# Main.net
KiCad netlist of a schematic drawn in Altium Designer
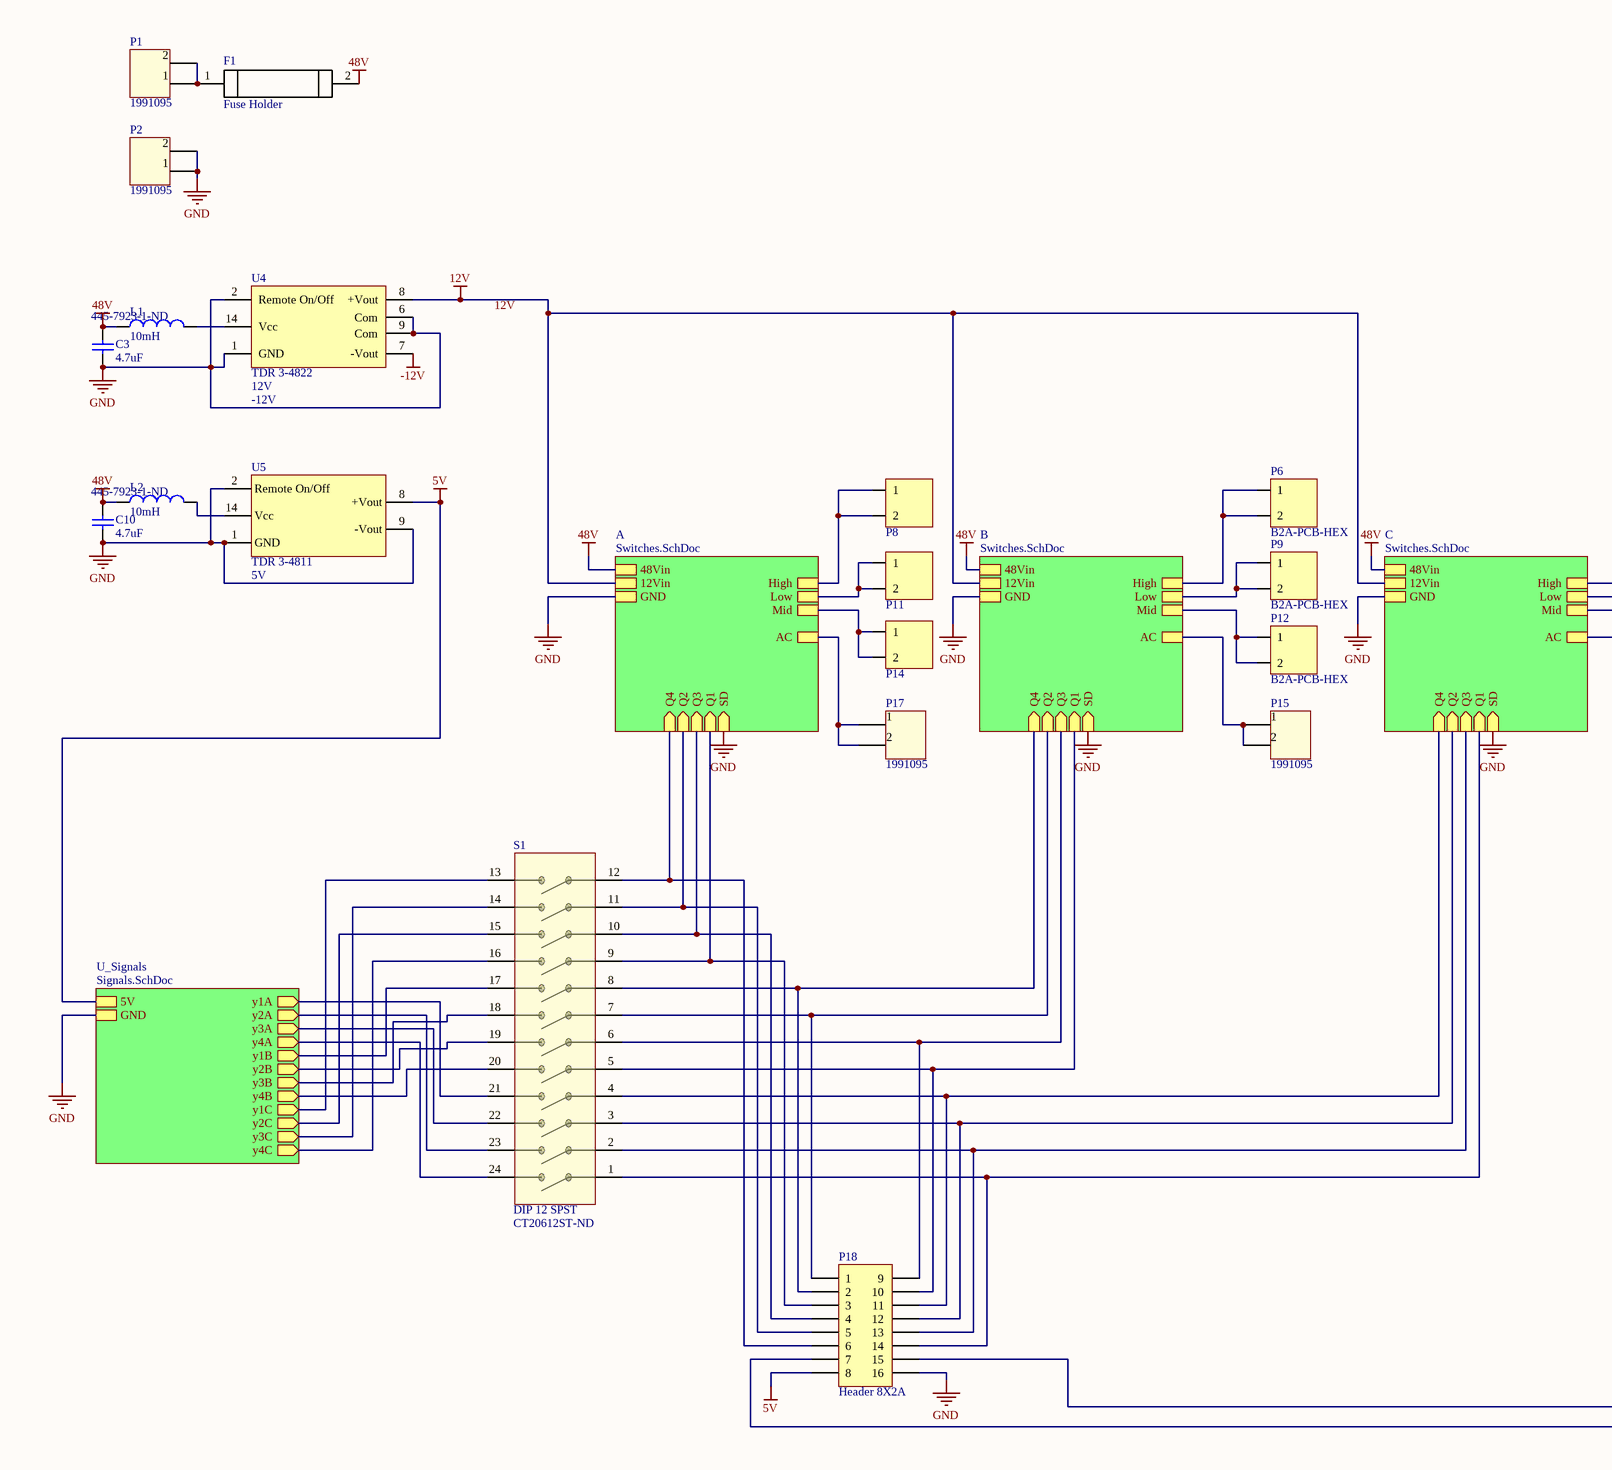
[diagram p0: Main.SchDoc, left]
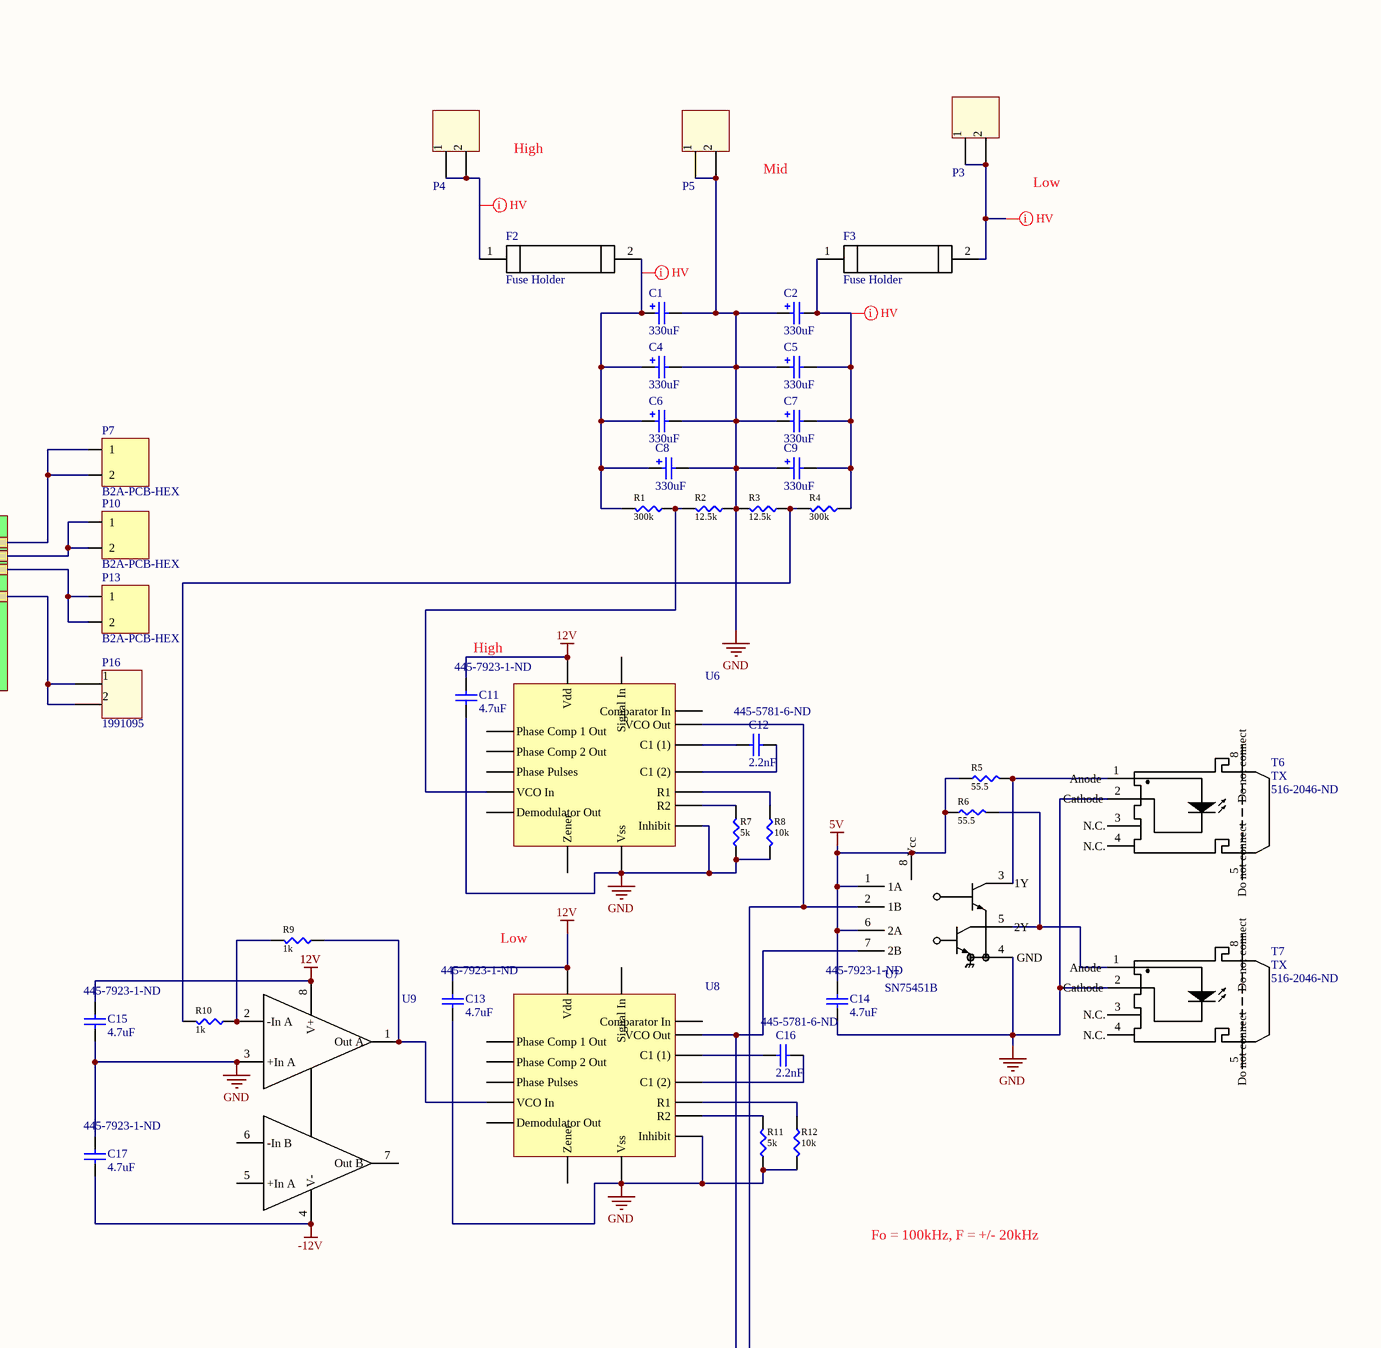
[diagram p1: Main.SchDoc, right]

(export (version "E")
  (design (tool "Eeschema 10.0.6"))
  (components
    (comp (ref "C1")
      (value "330uF")
      (footprint "LGW2G331MELB40")
      (description "Polarized Capacitor (Radial)")
      (fields
        (field (name "MANUFACTURER") "Nichicon")
        (field (name "MANUFACTURER PART NUMBER") "LGW2G331MELB40")
        (field (name "PUBLISHER") "Altium Limited")
      )
      (libsource (lib "T-Type Converter") (part "Cap Pol1"))
    )
    (comp (ref "C2")
      (value "330uF")
      (footprint "LGW2G331MELB40")
      (description "Polarized Capacitor (Radial)")
      (fields
        (field (name "MANUFACTURER") "Nichicon")
        (field (name "MANUFACTURER PART NUMBER") "LGW2G331MELB40")
        (field (name "PUBLISHER") "Altium Limited")
      )
      (libsource (lib "T-Type Converter") (part "Cap Pol1"))
    )
    (comp (ref "C3")
      (value "4.7uF")
      (footprint "C4532")
      (description "Capacitor")
      (fields
        (field (name "SUPPLIER PART NUMBER 1") "445-7923-1-ND")
        (field (name "MANUFACTURER") "TDK")
        (field (name "MANUFACTURER PART NUMBER") "CGA8N3X7S2A475K230KB")
        (field (name "PUBLISHER") "Altium Limited")
      )
      (libsource (lib "T-Type Converter") (part "Cap"))
    )
    (comp (ref "C4")
      (value "330uF")
      (footprint "LGW2G331MELB40")
      (description "Polarized Capacitor (Radial)")
      (fields
        (field (name "MANUFACTURER") "Nichicon")
        (field (name "MANUFACTURER PART NUMBER") "LGW2G331MELB40")
        (field (name "PUBLISHER") "Altium Limited")
      )
      (libsource (lib "T-Type Converter") (part "Cap Pol1"))
    )
    (comp (ref "C5")
      (value "330uF")
      (footprint "LGW2G331MELB40")
      (description "Polarized Capacitor (Radial)")
      (fields
        (field (name "MANUFACTURER") "Nichicon")
        (field (name "MANUFACTURER PART NUMBER") "LGW2G331MELB40")
        (field (name "PUBLISHER") "Altium Limited")
      )
      (libsource (lib "T-Type Converter") (part "Cap Pol1"))
    )
    (comp (ref "C6")
      (value "330uF")
      (footprint "LGW2G331MELB40")
      (description "Polarized Capacitor (Radial)")
      (fields
        (field (name "MANUFACTURER") "Nichicon")
        (field (name "MANUFACTURER PART NUMBER") "LGW2G331MELB40")
        (field (name "PUBLISHER") "Altium Limited")
      )
      (libsource (lib "T-Type Converter") (part "Cap Pol1"))
    )
    (comp (ref "C7")
      (value "330uF")
      (footprint "LGW2G331MELB40")
      (description "Polarized Capacitor (Radial)")
      (fields
        (field (name "MANUFACTURER") "Nichicon")
        (field (name "MANUFACTURER PART NUMBER") "LGW2G331MELB40")
        (field (name "PUBLISHER") "Altium Limited")
      )
      (libsource (lib "T-Type Converter") (part "Cap Pol1"))
    )
    (comp (ref "C8")
      (value "330uF")
      (footprint "LGW2G331MELB40")
      (description "Polarized Capacitor (Radial)")
      (fields
        (field (name "MANUFACTURER") "Nichicon")
        (field (name "MANUFACTURER PART NUMBER") "LGW2G331MELB40")
        (field (name "PUBLISHER") "Altium Limited")
      )
      (libsource (lib "T-Type Converter") (part "Cap Pol1"))
    )
    (comp (ref "C9")
      (value "330uF")
      (footprint "LGW2G331MELB40")
      (description "Polarized Capacitor (Radial)")
      (fields
        (field (name "MANUFACTURER") "Nichicon")
        (field (name "MANUFACTURER PART NUMBER") "LGW2G331MELB40")
        (field (name "PUBLISHER") "Altium Limited")
      )
      (libsource (lib "T-Type Converter") (part "Cap Pol1"))
    )
    (comp (ref "C10")
      (value "4.7uF")
      (footprint "C4532")
      (description "Capacitor")
      (fields
        (field (name "SUPPLIER PART NUMBER 1") "445-7923-1-ND")
        (field (name "MANUFACTURER") "TDK")
        (field (name "MANUFACTURER PART NUMBER") "CGA8N3X7S2A475K230KB")
        (field (name "PUBLISHER") "Altium Limited")
      )
      (libsource (lib "T-Type Converter") (part "Cap"))
    )
    (comp (ref "C11")
      (value "4.7uF")
      (footprint "C4532")
      (description "Capacitor")
      (fields
        (field (name "SUPPLIER PART NUMBER 1") "445-7923-1-ND")
        (field (name "MANUFACTURER") "TDK")
        (field (name "MANUFACTURER PART NUMBER") "CGA8N3X7S2A475K230KB")
        (field (name "PUBLISHER") "Altium Limited")
      )
      (libsource (lib "T-Type Converter") (part "Cap"))
    )
    (comp (ref "C12")
      (value "2.2nF")
      (footprint "R_1206")
      (description "Capacitor")
      (fields
        (field (name "SUPPLIER PART NUMBER 1") "445-5781-6-ND")
        (field (name "MANUFACTURER") "TDK")
        (field (name "MANUFACTURER PART NUMBER") "CGA5C4C0G2J221J060AA")
      )
      (libsource (lib "T-Type Converter") (part "Cap"))
    )
    (comp (ref "C13")
      (value "4.7uF")
      (footprint "C4532")
      (description "Capacitor")
      (fields
        (field (name "SUPPLIER PART NUMBER 1") "445-7923-1-ND")
        (field (name "MANUFACTURER") "TDK")
        (field (name "MANUFACTURER PART NUMBER") "CGA8N3X7S2A475K230KB")
        (field (name "PUBLISHER") "Altium Limited")
      )
      (libsource (lib "T-Type Converter") (part "Cap"))
    )
    (comp (ref "C14")
      (value "4.7uF")
      (footprint "C4532")
      (description "Capacitor")
      (fields
        (field (name "SUPPLIER PART NUMBER 1") "445-7923-1-ND")
        (field (name "MANUFACTURER") "TDK")
        (field (name "MANUFACTURER PART NUMBER") "CGA8N3X7S2A475K230KB")
        (field (name "PUBLISHER") "Altium Limited")
      )
      (libsource (lib "T-Type Converter") (part "Cap"))
    )
    (comp (ref "C15")
      (value "4.7uF")
      (footprint "C4532")
      (description "Capacitor")
      (fields
        (field (name "SUPPLIER PART NUMBER 1") "445-7923-1-ND")
        (field (name "MANUFACTURER") "TDK")
        (field (name "MANUFACTURER PART NUMBER") "CGA8N3X7S2A475K230KB")
        (field (name "PUBLISHER") "Altium Limited")
      )
      (libsource (lib "T-Type Converter") (part "Cap"))
    )
    (comp (ref "C16")
      (value "2.2nF")
      (footprint "R_1206")
      (description "Capacitor")
      (fields
        (field (name "SUPPLIER PART NUMBER 1") "445-5781-6-ND")
        (field (name "MANUFACTURER") "TDK")
        (field (name "MANUFACTURER PART NUMBER") "CGA5C4C0G2J221J060AA")
      )
      (libsource (lib "T-Type Converter") (part "Cap"))
    )
    (comp (ref "C17")
      (value "4.7uF")
      (footprint "C4532")
      (description "Capacitor")
      (fields
        (field (name "SUPPLIER PART NUMBER 1") "445-7923-1-ND")
        (field (name "MANUFACTURER") "TDK")
        (field (name "MANUFACTURER PART NUMBER") "CGA8N3X7S2A475K230KB")
        (field (name "PUBLISHER") "Altium Limited")
      )
      (libsource (lib "T-Type Converter") (part "Cap"))
    )
    (comp (ref "F1")
      (value "Fuse Holder")
      (footprint "Small Fuse Holder")
      (fields
        (field (name "MANUFACTURER") "Littelfuse")
        (field (name "MANUFACTURER PART NUMBER") "01220093Z")
        (field (name "VOLTAGE") "250V")
      )
      (libsource (lib "T-Type Converter") (part "Fuse Holder"))
    )
    (comp (ref "F2")
      (value "Fuse Holder")
      (footprint "Fuse footprint")
      (fields
        (field (name "MANUFACTURER") "Littelfuse")
        (field (name "MANUFACTURER PART NUMBER") "01220093Z")
        (field (name "VOLTAGE") "250V")
      )
      (libsource (lib "T-Type Converter") (part "Fuse Holder"))
    )
    (comp (ref "F3")
      (value "Fuse Holder")
      (footprint "Fuse footprint")
      (fields
        (field (name "MANUFACTURER") "Littelfuse")
        (field (name "MANUFACTURER PART NUMBER") "01220093Z")
        (field (name "VOLTAGE") "250V")
      )
      (libsource (lib "T-Type Converter") (part "Fuse Holder"))
    )
    (comp (ref "L1")
      (value "10mH")
      (footprint "TCK-047")
      (description "Inductor")
      (fields (field (name "PUBLISHER") "Altium Limited"))
      (libsource (lib "Miscellaneous Devices") (part "Inductor"))
    )
    (comp (ref "L2")
      (value "10mH")
      (footprint "TCK-047")
      (description "Inductor")
      (fields (field (name "PUBLISHER") "Altium Limited"))
      (libsource (lib "Miscellaneous Devices") (part "Inductor"))
    )
    (comp (ref "P1")
      (value "1991095")
      (footprint "Terminal Pad")
      (description "2 way terminal block")
      (fields (field (name "MANUFACTURER") "Phoenix Contact") (field (name "VOLTAGE") "300V"))
      (libsource (lib "") (part "Terminal Block 2_1"))
    )
    (comp (ref "P2")
      (value "1991095")
      (footprint "Terminal Pad")
      (description "2 way terminal block")
      (fields (field (name "MANUFACTURER") "Phoenix Contact") (field (name "VOLTAGE") "300V"))
      (libsource (lib "") (part "Terminal Block 2_1"))
    )
    (comp (ref "P3")
      (value "1991095")
      (footprint "Terminal Pad")
      (description "2 way terminal block")
      (fields (field (name "MANUFACTURER") "Phoenix Contact") (field (name "VOLTAGE") "300V"))
      (libsource (lib "") (part "Terminal Block 2_2"))
    )
    (comp (ref "P4")
      (value "1991095")
      (footprint "Terminal Pad")
      (description "2 way terminal block")
      (fields (field (name "MANUFACTURER") "Phoenix Contact") (field (name "VOLTAGE") "300V"))
      (libsource (lib "") (part "Terminal Block 2_2"))
    )
    (comp (ref "P5")
      (value "1991095")
      (footprint "Terminal Pad")
      (description "2 way terminal block")
      (fields (field (name "MANUFACTURER") "Phoenix Contact") (field (name "VOLTAGE") "300V"))
      (libsource (lib "") (part "Terminal Block 2_2"))
    )
    (comp (ref "P6")
      (value "B2A-PCB-HEX")
      (footprint "Terminal Pad")
      (libsource (lib "T-Type Converter") (part "B2A-PCB-HEX"))
    )
    (comp (ref "P7")
      (value "B2A-PCB-HEX")
      (footprint "Terminal Pad")
      (libsource (lib "T-Type Converter") (part "B2A-PCB-HEX"))
    )
    (comp (ref "P8")
      (value "B2A-PCB-HEX")
      (footprint "Terminal Pad")
      (libsource (lib "T-Type Converter") (part "B2A-PCB-HEX"))
    )
    (comp (ref "P9")
      (value "B2A-PCB-HEX")
      (footprint "Terminal Pad")
      (libsource (lib "T-Type Converter") (part "B2A-PCB-HEX"))
    )
    (comp (ref "P10")
      (value "B2A-PCB-HEX")
      (footprint "Terminal Pad")
      (libsource (lib "T-Type Converter") (part "B2A-PCB-HEX"))
    )
    (comp (ref "P11")
      (value "B2A-PCB-HEX")
      (footprint "Terminal Pad")
      (libsource (lib "T-Type Converter") (part "B2A-PCB-HEX"))
    )
    (comp (ref "P12")
      (value "B2A-PCB-HEX")
      (footprint "Terminal Pad")
      (libsource (lib "T-Type Converter") (part "B2A-PCB-HEX"))
    )
    (comp (ref "P13")
      (value "B2A-PCB-HEX")
      (footprint "Terminal Pad")
      (libsource (lib "T-Type Converter") (part "B2A-PCB-HEX"))
    )
    (comp (ref "P14")
      (value "B2A-PCB-HEX")
      (footprint "Terminal Pad")
      (libsource (lib "T-Type Converter") (part "B2A-PCB-HEX"))
    )
    (comp (ref "P15")
      (value "1991095")
      (footprint "Terminal Pad")
      (description "2 way terminal block")
      (fields (field (name "MANUFACTURER") "Phoenix Contact") (field (name "VOLTAGE") "300V"))
      (libsource (lib "T-Type Converter") (part "Terminal Block 2"))
    )
    (comp (ref "P16")
      (value "1991095")
      (footprint "Terminal Pad")
      (description "2 way terminal block")
      (fields (field (name "MANUFACTURER") "Phoenix Contact") (field (name "VOLTAGE") "300V"))
      (libsource (lib "T-Type Converter") (part "Terminal Block 2"))
    )
    (comp (ref "P17")
      (value "1991095")
      (footprint "Terminal Pad")
      (description "2 way terminal block")
      (fields (field (name "MANUFACTURER") "Phoenix Contact") (field (name "VOLTAGE") "300V"))
      (libsource (lib "T-Type Converter") (part "Terminal Block 2"))
    )
    (comp (ref "P18")
      (value "Header 8X2A")
      (footprint "302-S161")
      (description "Header, 8-Pin, Dual row")
      (fields
        (field (name "MANUFACTURER") "On-Shore Technology")
        (field (name "MANUFACTURER PART NUMBER") "302-S161")
        (field (name "PUBLISHER") "Altium Limited")
      )
      (libsource (lib "Miscellaneous Connectors") (part "Header 8X2A"))
    )
    (comp (ref "R1")
      (value "300k")
      (footprint "R_1206")
      (description "RES SMD 1% 1/4W 1206")
      (fields
        (field (name "MANUFACTURER") "Panasonic Electronic Components")
        (field (name "MANUFACTURER PART NUMBER") "ERJ-8ENF9101V")
      )
      (libsource (lib "T-Type Converter") (part "RES_SMD1"))
    )
    (comp (ref "R2")
      (value "12.5k")
      (footprint "R_1206")
      (description "RES SMD 1% 1/4W 1206")
      (fields
        (field (name "MANUFACTURER") "Panasonic Electronic Components")
        (field (name "MANUFACTURER PART NUMBER") "ERJ-8ENF9101V")
      )
      (libsource (lib "T-Type Converter") (part "RES_SMD1"))
    )
    (comp (ref "R3")
      (value "12.5k")
      (footprint "R_1206")
      (description "RES SMD 1% 1/4W 1206")
      (fields
        (field (name "MANUFACTURER") "Panasonic Electronic Components")
        (field (name "MANUFACTURER PART NUMBER") "ERJ-8ENF9101V")
      )
      (libsource (lib "T-Type Converter") (part "RES_SMD1"))
    )
    (comp (ref "R4")
      (value "300k")
      (footprint "R_1206")
      (description "RES SMD 1% 1/4W 1206")
      (fields
        (field (name "MANUFACTURER") "Panasonic Electronic Components")
        (field (name "MANUFACTURER PART NUMBER") "ERJ-8ENF9101V")
      )
      (libsource (lib "T-Type Converter") (part "RES_SMD1"))
    )
    (comp (ref "R5")
      (value "55.5")
      (footprint "R_1206")
      (description "RES SMD 1% 1/4W 1206")
      (fields
        (field (name "MANUFACTURER") "Panasonic Electronic Components")
        (field (name "MANUFACTURER PART NUMBER") "ERJ-8ENF9101V")
      )
      (libsource (lib "T-Type Converter") (part "RES_SMD1"))
    )
    (comp (ref "R6")
      (value "55.5")
      (footprint "R_1206")
      (description "RES SMD 1% 1/4W 1206")
      (fields
        (field (name "MANUFACTURER") "Panasonic Electronic Components")
        (field (name "MANUFACTURER PART NUMBER") "ERJ-8ENF9101V")
      )
      (libsource (lib "T-Type Converter") (part "RES_SMD1"))
    )
    (comp (ref "R7")
      (value "5k")
      (footprint "R_1206")
      (description "RES SMD 1% 1/4W 1206")
      (fields
        (field (name "MANUFACTURER") "Panasonic Electronic Components")
        (field (name "MANUFACTURER PART NUMBER") "ERJ-8ENF9101V")
      )
      (libsource (lib "T-Type Converter") (part "RES_SMD1"))
    )
    (comp (ref "R8")
      (value "10k")
      (footprint "R_1206")
      (description "RES SMD 1% 1/4W 1206")
      (fields
        (field (name "MANUFACTURER") "Panasonic Electronic Components")
        (field (name "MANUFACTURER PART NUMBER") "ERJ-8ENF9101V")
      )
      (libsource (lib "T-Type Converter") (part "RES_SMD1"))
    )
    (comp (ref "R9")
      (value "1k")
      (footprint "R_1206")
      (description "RES SMD 1% 1/4W 1206")
      (fields
        (field (name "MANUFACTURER") "Panasonic Electronic Components")
        (field (name "MANUFACTURER PART NUMBER") "ERJ-8ENF9101V")
      )
      (libsource (lib "T-Type Converter") (part "RES_SMD1"))
    )
    (comp (ref "R10")
      (value "1k")
      (footprint "R_1206")
      (description "RES SMD 1% 1/4W 1206")
      (fields
        (field (name "MANUFACTURER") "Panasonic Electronic Components")
        (field (name "MANUFACTURER PART NUMBER") "ERJ-8ENF9101V")
      )
      (libsource (lib "T-Type Converter") (part "RES_SMD1"))
    )
    (comp (ref "R11")
      (value "5k")
      (footprint "R_1206")
      (description "RES SMD 1% 1/4W 1206")
      (fields
        (field (name "MANUFACTURER") "Panasonic Electronic Components")
        (field (name "MANUFACTURER PART NUMBER") "ERJ-8ENF9101V")
      )
      (libsource (lib "T-Type Converter") (part "RES_SMD1"))
    )
    (comp (ref "R12")
      (value "10k")
      (footprint "R_1206")
      (description "RES SMD 1% 1/4W 1206")
      (fields
        (field (name "MANUFACTURER") "Panasonic Electronic Components")
        (field (name "MANUFACTURER PART NUMBER") "ERJ-8ENF9101V")
      )
      (libsource (lib "T-Type Converter") (part "RES_SMD1"))
    )
    (comp (ref "S1")
      (value "DIP 12 SPST")
      (footprint "DIP12 SPST")
      (fields
        (field (name "MANUFACTURER") "CTS Electrocomponents")
        (field (name "MANUFACTURER PART NUMBER") "206-12ST")
        (field (name "SUPPLIER PART NUMBER 1") "CT20612ST-ND")
      )
      (libsource (lib "T-Type Converter") (part "DIP 12 SPST"))
    )
    (comp (ref "T6")
      (value "TX")
      (footprint "Optics")
      (description "Otical Transmitter")
      (fields
        (field (name "MANUFACTURER") "Broadcom Avago")
        (field (name "MANUFACTURER PART NUMBER") "HFBR-1524Z")
        (field (name "SUPPLIER PART NUMBER 1") "516-2046-ND")
      )
      (libsource (lib "T-Type Converter") (part "HFBR-1524Z"))
    )
    (comp (ref "T7")
      (value "TX")
      (footprint "Optics")
      (description "Otical Transmitter")
      (fields
        (field (name "MANUFACTURER") "Broadcom Avago")
        (field (name "MANUFACTURER PART NUMBER") "HFBR-1524Z")
        (field (name "SUPPLIER PART NUMBER 1") "516-2046-ND")
      )
      (libsource (lib "T-Type Converter") (part "HFBR-1524Z"))
    )
    (comp (ref "U4")
      (value "TDR 3-4822")
      (footprint "PID DC-DC Converter - duplicate")
      (description "48 +/-12V Converter")
      (fields
        (field (name "MANUFACTURER") "Traco Power")
        (field (name "MANUFACTURER PART NUMBER") "TDR3-4822")
        (field (name "VOLTAGE - OUTPUT 1") "12V")
        (field (name "VOLTAGE - OUTPUT 2") "-12V")
      )
      (libsource (lib "T-Type Converter") (part "TDR 3-4822"))
    )
    (comp (ref "U5")
      (value "TDR 3-4811")
      (footprint "PID DC-DC Converter - duplicate")
      (description "48V-5V Converter")
      (fields
        (field (name "MANUFACTURER") "Traco Power")
        (field (name "MANUFACTURER PART NUMBER") "TDR3-4811")
        (field (name "VOLTAGE - OUTPUT 1") "5V")
      )
      (libsource (lib "T-Type Converter") (part "TDR 3-4811"))
    )
    (comp (ref "U6")
      (value "CD4046B")
      (footprint "DIP16")
      (description "VCO")
      (fields
        (field (name "MANUFACTURER") "Texas Instruments")
        (field (name "MANUFACTURER PART NUMBER") "CD4046BE")
      )
      (libsource (lib "T-Type Converter") (part "CD4046B"))
    )
    (comp (ref "U7")
      (value "SN75451B")
      (footprint "R-PDIP-T8")
      (description "Dual Peripheral Drivers")
      (fields
        (field (name "MANUFACTURER") "Texas Instruments")
        (field (name "MANUFACTURER PART NUMBER") "SN75451BP")
      )
      (libsource (lib "T-Type Converter") (part "SN75451B"))
    )
    (comp (ref "U8")
      (value "CD4046B")
      (footprint "DIP16")
      (description "VCO")
      (fields
        (field (name "MANUFACTURER") "Texas Instruments")
        (field (name "MANUFACTURER PART NUMBER") "CD4046BE")
      )
      (libsource (lib "T-Type Converter") (part "CD4046B"))
    )
    (comp (ref "U9")
      (value "LT1057CN8")
      (footprint "N8 PDIP")
      (description "Dual Op-Amp")
      (fields
        (field (name "MANUFACTURER") "STMicroelectronics")
        (field (name "MANUFACTURER PART NUMBER") "LMV321LICT")
      )
      (libsource (lib "T-Type Converter") (part "LT1057CN8"))
    )
  )
  (nets
    (net (code "1") (name "-12V") (class "Default")
      (node (ref "C17") (pin "1") (pinfunction "1_1") (pintype "passive"))
      (node (ref "U4") (pin "7") (pinfunction "-Vout_7") (pintype "passive"))
      (node (ref "U9") (pin "4") (pinfunction "V-_4") (pintype "power_in"))
    )
    (net (code "2") (name "/AC") (class "Default")
      (node (ref "P16") (pin "1") (pintype "power_in"))
      (node (ref "P16") (pin "2") (pintype "power_in"))
    )
    (net (code "3") (name "/AC_1") (class "Default")
      (node (ref "P17") (pin "1") (pintype "power_in"))
      (node (ref "P17") (pin "2") (pintype "power_in"))
    )
    (net (code "4") (name "/AC_2") (class "Default")
      (node (ref "P15") (pin "1") (pintype "power_in"))
      (node (ref "P15") (pin "2") (pintype "power_in"))
    )
    (net (code "5") (name "/High") (class "Default")
      (node (ref "P7") (pin "1") (pinfunction "1_1") (pintype "passive"))
      (node (ref "P7") (pin "2") (pinfunction "2_2") (pintype "passive"))
    )
    (net (code "6") (name "/High_1") (class "Default")
      (node (ref "P8") (pin "1") (pinfunction "1_1") (pintype "passive"))
      (node (ref "P8") (pin "2") (pinfunction "2_2") (pintype "passive"))
    )
    (net (code "7") (name "/High_2") (class "Default")
      (node (ref "P6") (pin "1") (pinfunction "1_1") (pintype "passive"))
      (node (ref "P6") (pin "2") (pinfunction "2_2") (pintype "passive"))
    )
    (net (code "8") (name "/Low") (class "Default")
      (node (ref "P10") (pin "1") (pinfunction "1_1") (pintype "passive"))
      (node (ref "P10") (pin "2") (pinfunction "2_2") (pintype "passive"))
    )
    (net (code "9") (name "/Low_1") (class "Default")
      (node (ref "P11") (pin "1") (pinfunction "1_1") (pintype "passive"))
      (node (ref "P11") (pin "2") (pinfunction "2_2") (pintype "passive"))
    )
    (net (code "10") (name "/Low_2") (class "Default")
      (node (ref "P9") (pin "1") (pinfunction "1_1") (pintype "passive"))
      (node (ref "P9") (pin "2") (pinfunction "2_2") (pintype "passive"))
    )
    (net (code "11") (name "/Mid") (class "Default")
      (node (ref "P13") (pin "1") (pinfunction "1_1") (pintype "passive"))
      (node (ref "P13") (pin "2") (pinfunction "2_2") (pintype "passive"))
    )
    (net (code "12") (name "/Mid_1") (class "Default")
      (node (ref "P14") (pin "1") (pinfunction "1_1") (pintype "passive"))
      (node (ref "P14") (pin "2") (pinfunction "2_2") (pintype "passive"))
    )
    (net (code "13") (name "/Mid_2") (class "Default")
      (node (ref "P12") (pin "1") (pinfunction "1_1") (pintype "passive"))
      (node (ref "P12") (pin "2") (pinfunction "2_2") (pintype "passive"))
    )
    (net (code "14") (name "/Q1") (class "Default")
      (node (ref "P18") (pin "14") (pinfunction "14_14") (pintype "passive"))
      (node (ref "S1") (pin "1") (pinfunction "1_1") (pintype "power_in"))
    )
    (net (code "15") (name "/Q1_1") (class "Default")
      (node (ref "P18") (pin "10") (pinfunction "10_10") (pintype "passive"))
      (node (ref "S1") (pin "5") (pinfunction "5_5") (pintype "power_in"))
    )
    (net (code "16") (name "/Q1_2") (class "Default")
      (node (ref "P18") (pin "3") (pinfunction "3_3") (pintype "passive"))
      (node (ref "S1") (pin "9") (pinfunction "9_9") (pintype "power_in"))
    )
    (net (code "17") (name "/Q2") (class "Default")
      (node (ref "P18") (pin "5") (pinfunction "5_5") (pintype "passive"))
      (node (ref "S1") (pin "11") (pinfunction "11_11") (pintype "power_in"))
    )
    (net (code "18") (name "/Q2_1") (class "Default")
      (node (ref "P18") (pin "1") (pinfunction "1_1") (pintype "passive"))
      (node (ref "S1") (pin "7") (pinfunction "7_7") (pintype "power_in"))
    )
    (net (code "19") (name "/Q2_2") (class "Default")
      (node (ref "P18") (pin "12") (pinfunction "12_12") (pintype "passive"))
      (node (ref "S1") (pin "3") (pinfunction "3_3") (pintype "power_in"))
    )
    (net (code "20") (name "/Q3") (class "Default")
      (node (ref "P18") (pin "4") (pinfunction "4_4") (pintype "passive"))
      (node (ref "S1") (pin "10") (pinfunction "10_10") (pintype "power_in"))
    )
    (net (code "21") (name "/Q3_1") (class "Default")
      (node (ref "P18") (pin "9") (pinfunction "9_9") (pintype "passive"))
      (node (ref "S1") (pin "6") (pinfunction "6_6") (pintype "power_in"))
    )
    (net (code "22") (name "/Q3_2") (class "Default")
      (node (ref "P18") (pin "13") (pinfunction "13_13") (pintype "passive"))
      (node (ref "S1") (pin "2") (pinfunction "2_2") (pintype "power_in"))
    )
    (net (code "23") (name "/Q4") (class "Default")
      (node (ref "P18") (pin "2") (pinfunction "2_2") (pintype "passive"))
      (node (ref "S1") (pin "8") (pinfunction "8_8") (pintype "power_in"))
    )
    (net (code "24") (name "/Q4_1") (class "Default")
      (node (ref "P18") (pin "11") (pinfunction "11_11") (pintype "passive"))
      (node (ref "S1") (pin "4") (pinfunction "4_4") (pintype "power_in"))
    )
    (net (code "25") (name "/Q4_2") (class "Default")
      (node (ref "P18") (pin "6") (pinfunction "6_6") (pintype "passive"))
      (node (ref "S1") (pin "12") (pinfunction "12_12") (pintype "power_in"))
    )
    (net (code "26") (name "/y1A") (class "Default")
      (node (ref "S1") (pin "21") (pinfunction "21_21") (pintype "power_in"))
    )
    (net (code "27") (name "/y1B") (class "Default")
      (node (ref "S1") (pin "17") (pinfunction "17_17") (pintype "power_in"))
    )
    (net (code "28") (name "/y1C") (class "Default")
      (node (ref "S1") (pin "13") (pinfunction "13_13") (pintype "power_in"))
    )
    (net (code "29") (name "/y2A") (class "Default")
      (node (ref "S1") (pin "23") (pinfunction "23_23") (pintype "power_in"))
    )
    (net (code "30") (name "/y2B") (class "Default")
      (node (ref "S1") (pin "19") (pinfunction "19_19") (pintype "power_in"))
    )
    (net (code "31") (name "/y2C") (class "Default")
      (node (ref "S1") (pin "15") (pinfunction "15_15") (pintype "power_in"))
    )
    (net (code "32") (name "/y3A") (class "Default")
      (node (ref "S1") (pin "22") (pinfunction "22_22") (pintype "power_in"))
    )
    (net (code "33") (name "/y3B") (class "Default")
      (node (ref "S1") (pin "18") (pinfunction "18_18") (pintype "power_in"))
    )
    (net (code "34") (name "/y3C") (class "Default")
      (node (ref "S1") (pin "14") (pinfunction "14_14") (pintype "power_in"))
    )
    (net (code "35") (name "/y4A") (class "Default")
      (node (ref "S1") (pin "24") (pinfunction "24_24") (pintype "power_in"))
    )
    (net (code "36") (name "/y4B") (class "Default")
      (node (ref "S1") (pin "20") (pinfunction "20_20") (pintype "power_in"))
    )
    (net (code "37") (name "/y4C") (class "Default")
      (node (ref "S1") (pin "16") (pinfunction "16_16") (pintype "power_in"))
    )
    (net (code "38") (name "5V") (class "Default")
      (node (ref "C14") (pin "2") (pinfunction "2_2") (pintype "passive"))
      (node (ref "P18") (pin "8") (pinfunction "8_8") (pintype "passive"))
      (node (ref "R5") (pin "2") (pinfunction "2_2") (pintype "passive"))
      (node (ref "R6") (pin "2") (pinfunction "2_2") (pintype "passive"))
      (node (ref "U5") (pin "8") (pinfunction "+Vout_8") (pintype "passive"))
      (node (ref "U7") (pin "1") (pinfunction "1A_1") (pintype "power_in"))
      (node (ref "U7") (pin "6") (pinfunction "2A_6") (pintype "power_in"))
      (node (ref "U7") (pin "8") (pinfunction "Vcc_8") (pintype "power_in"))
    )
    (net (code "39") (name "12V") (class "Default")
      (node (ref "C11") (pin "2") (pinfunction "2_2") (pintype "passive"))
      (node (ref "C13") (pin "2") (pinfunction "2_2") (pintype "passive"))
      (node (ref "C15") (pin "2") (pinfunction "2_2") (pintype "passive"))
      (node (ref "U4") (pin "8") (pinfunction "+Vout_8") (pintype "passive"))
      (node (ref "U6") (pin "16") (pinfunction "Vdd_16") (pintype "passive"))
      (node (ref "U8") (pin "16") (pinfunction "Vdd_16") (pintype "passive"))
      (node (ref "U9") (pin "8") (pinfunction "V+_8") (pintype "power_in"))
    )
    (net (code "40") (name "48V") (class "Default")
      (node (ref "C10") (pin "2") (pinfunction "2_2") (pintype "passive"))
      (node (ref "C3") (pin "2") (pinfunction "2_2") (pintype "passive"))
      (node (ref "F1") (pin "2") (pintype "power_in"))
      (node (ref "L1") (pin "1") (pinfunction "1_1") (pintype "passive"))
      (node (ref "L2") (pin "1") (pinfunction "1_1") (pintype "passive"))
    )
    (net (code "41") (name "GND") (class "Default")
      (node (ref "C1") (pin "2") (pinfunction "2_2") (pintype "passive"))
      (node (ref "C10") (pin "1") (pinfunction "1_1") (pintype "passive"))
      (node (ref "C11") (pin "1") (pinfunction "1_1") (pintype "passive"))
      (node (ref "C13") (pin "1") (pinfunction "1_1") (pintype "passive"))
      (node (ref "C14") (pin "1") (pinfunction "1_1") (pintype "passive"))
      (node (ref "C15") (pin "1") (pinfunction "1_1") (pintype "passive"))
      (node (ref "C17") (pin "2") (pinfunction "2_2") (pintype "passive"))
      (node (ref "C2") (pin "1") (pinfunction "1_1") (pintype "passive"))
      (node (ref "C3") (pin "1") (pinfunction "1_1") (pintype "passive"))
      (node (ref "C4") (pin "2") (pinfunction "2_2") (pintype "passive"))
      (node (ref "C5") (pin "1") (pinfunction "1_1") (pintype "passive"))
      (node (ref "C6") (pin "2") (pinfunction "2_2") (pintype "passive"))
      (node (ref "C7") (pin "1") (pinfunction "1_1") (pintype "passive"))
      (node (ref "C8") (pin "2") (pinfunction "2_2") (pintype "passive"))
      (node (ref "C9") (pin "1") (pinfunction "1_1") (pintype "passive"))
      (node (ref "P18") (pin "16") (pinfunction "16_16") (pintype "passive"))
      (node (ref "P2") (pin "1") (pintype "power_in"))
      (node (ref "P2") (pin "2") (pintype "power_in"))
      (node (ref "P5") (pin "1") (pintype "power_in"))
      (node (ref "P5") (pin "2") (pintype "power_in"))
      (node (ref "R11") (pin "2") (pinfunction "2_2") (pintype "passive"))
      (node (ref "R12") (pin "1") (pinfunction "1_1") (pintype "passive"))
      (node (ref "R2") (pin "2") (pinfunction "2_2") (pintype "passive"))
      (node (ref "R3") (pin "1") (pinfunction "1_1") (pintype "passive"))
      (node (ref "R7") (pin "2") (pinfunction "2_2") (pintype "passive"))
      (node (ref "R8") (pin "1") (pinfunction "1_1") (pintype "passive"))
      (node (ref "T6") (pin "2") (pinfunction "Cathode_2") (pintype "passive"))
      (node (ref "T7") (pin "2") (pinfunction "Cathode_2") (pintype "passive"))
      (node (ref "U4") (pin "1") (pinfunction "GND_1") (pintype "power_in"))
      (node (ref "U4") (pin "2") (pinfunction "Remote_On/Off_2") (pintype "passive"))
      (node (ref "U4") (pin "6") (pinfunction "Com_6") (pintype "power_in"))
      (node (ref "U4") (pin "9") (pinfunction "Com_9") (pintype "power_in"))
      (node (ref "U5") (pin "1") (pinfunction "GND_1") (pintype "power_in"))
      (node (ref "U5") (pin "2") (pinfunction "Remote_On/Off_2") (pintype "passive"))
      (node (ref "U5") (pin "9") (pinfunction "-Vout_9") (pintype "passive"))
      (node (ref "U6") (pin "5") (pinfunction "Inhibit_5") (pintype "passive"))
      (node (ref "U6") (pin "8") (pinfunction "Vss_8") (pintype "passive"))
      (node (ref "U7") (pin "4") (pinfunction "GND_4") (pintype "power_in"))
      (node (ref "U8") (pin "5") (pinfunction "Inhibit_5") (pintype "passive"))
      (node (ref "U8") (pin "8") (pinfunction "Vss_8") (pintype "passive"))
      (node (ref "U9") (pin "3") (pinfunction "+In_A_3") (pintype "power_in"))
    )
    (net (code "42") (name "Net-(C1-Pad1)") (class "Default")
      (node (ref "C1") (pin "1") (pinfunction "1_1") (pintype "passive"))
      (node (ref "C4") (pin "1") (pinfunction "1_1") (pintype "passive"))
      (node (ref "C6") (pin "1") (pinfunction "1_1") (pintype "passive"))
      (node (ref "C8") (pin "1") (pinfunction "1_1") (pintype "passive"))
      (node (ref "F2") (pin "2") (pintype "power_in"))
      (node (ref "R1") (pin "1") (pinfunction "1_1") (pintype "passive"))
    )
    (net (code "43") (name "Net-(C2-Pad2)") (class "Default")
      (node (ref "C2") (pin "2") (pinfunction "2_2") (pintype "passive"))
      (node (ref "C5") (pin "2") (pinfunction "2_2") (pintype "passive"))
      (node (ref "C7") (pin "2") (pinfunction "2_2") (pintype "passive"))
      (node (ref "C9") (pin "2") (pinfunction "2_2") (pintype "passive"))
      (node (ref "F3") (pin "1") (pintype "power_in"))
      (node (ref "R4") (pin "2") (pinfunction "2_2") (pintype "passive"))
    )
    (net (code "44") (name "Net-(F1-Pad1)") (class "Default")
      (node (ref "F1") (pin "1") (pintype "power_in"))
      (node (ref "P1") (pin "1") (pintype "power_in"))
      (node (ref "P1") (pin "2") (pintype "power_in"))
    )
    (net (code "45") (name "Net-(F2-Pad1)") (class "Default")
      (node (ref "F2") (pin "1") (pintype "power_in"))
      (node (ref "P4") (pin "1") (pintype "power_in"))
      (node (ref "P4") (pin "2") (pintype "power_in"))
    )
    (net (code "46") (name "Net-(F3-Pad2)") (class "Default")
      (node (ref "F3") (pin "2") (pintype "power_in"))
      (node (ref "P3") (pin "1") (pintype "power_in"))
      (node (ref "P3") (pin "2") (pintype "power_in"))
    )
    (net (code "47") (name "Net-(R10-Pad1)") (class "Default")
      (node (ref "R10") (pin "1") (pinfunction "1_1") (pintype "passive"))
      (node (ref "R3") (pin "2") (pinfunction "2_2") (pintype "passive"))
      (node (ref "R4") (pin "1") (pinfunction "1_1") (pintype "passive"))
    )
    (net (code "48") (name "Net-(T6-Anode)") (class "Default")
      (node (ref "R5") (pin "1") (pinfunction "1_1") (pintype "passive"))
      (node (ref "T6") (pin "1") (pinfunction "Anode_1") (pintype "passive"))
      (node (ref "U7") (pin "3") (pinfunction "1Y_3") (pintype "power_in"))
    )
    (net (code "49") (name "Net-(T7-Anode)") (class "Default")
      (node (ref "R6") (pin "1") (pinfunction "1_1") (pintype "passive"))
      (node (ref "T7") (pin "1") (pinfunction "Anode_1") (pintype "passive"))
      (node (ref "U7") (pin "5") (pinfunction "2Y_5") (pintype "power_in"))
    )
    (net (code "50") (name "Net-(U4-Vcc)") (class "Default")
      (node (ref "L1") (pin "2") (pinfunction "2_2") (pintype "passive"))
      (node (ref "U4") (pin "14") (pinfunction "Vcc_14") (pintype "passive"))
    )
    (net (code "51") (name "Net-(U5-Vcc)") (class "Default")
      (node (ref "L2") (pin "2") (pinfunction "2_2") (pintype "passive"))
      (node (ref "U5") (pin "14") (pinfunction "Vcc_14") (pintype "passive"))
    )
    (net (code "52") (name "Net-(U6-C1_(1))") (class "Default")
      (node (ref "C12") (pin "1") (pinfunction "1_1") (pintype "passive"))
      (node (ref "U6") (pin "6") (pinfunction "C1_(1)_6") (pintype "passive"))
    )
    (net (code "53") (name "Net-(U6-C1_(2))") (class "Default")
      (node (ref "C12") (pin "2") (pinfunction "2_2") (pintype "passive"))
      (node (ref "U6") (pin "7") (pinfunction "C1_(2)_7") (pintype "passive"))
    )
    (net (code "54") (name "Net-(U6-R1)") (class "Default")
      (node (ref "R8") (pin "2") (pinfunction "2_2") (pintype "passive"))
      (node (ref "U6") (pin "11") (pinfunction "R1_11") (pintype "passive"))
    )
    (net (code "55") (name "Net-(U6-R2)") (class "Default")
      (node (ref "R7") (pin "1") (pinfunction "1_1") (pintype "passive"))
      (node (ref "U6") (pin "12") (pinfunction "R2_12") (pintype "passive"))
    )
    (net (code "56") (name "Net-(U6-VCO_In)") (class "Default")
      (node (ref "R1") (pin "2") (pinfunction "2_2") (pintype "passive"))
      (node (ref "R2") (pin "1") (pinfunction "1_1") (pintype "passive"))
      (node (ref "U6") (pin "9") (pinfunction "VCO_In_9") (pintype "passive"))
    )
    (net (code "57") (name "Net-(U6-VCO_Out)") (class "Default")
      (node (ref "P18") (pin "7") (pinfunction "7_7") (pintype "passive"))
      (node (ref "U6") (pin "4") (pinfunction "VCO_Out_4") (pintype "passive"))
      (node (ref "U7") (pin "2") (pinfunction "1B_2") (pintype "power_in"))
    )
    (net (code "58") (name "Net-(U7-2B)") (class "Default")
      (node (ref "P18") (pin "15") (pinfunction "15_15") (pintype "passive"))
      (node (ref "U7") (pin "7") (pinfunction "2B_7") (pintype "power_in"))
      (node (ref "U8") (pin "4") (pinfunction "VCO_Out_4") (pintype "passive"))
    )
    (net (code "59") (name "Net-(U8-C1_(1))") (class "Default")
      (node (ref "C16") (pin "1") (pinfunction "1_1") (pintype "passive"))
      (node (ref "U8") (pin "6") (pinfunction "C1_(1)_6") (pintype "passive"))
    )
    (net (code "60") (name "Net-(U8-C1_(2))") (class "Default")
      (node (ref "C16") (pin "2") (pinfunction "2_2") (pintype "passive"))
      (node (ref "U8") (pin "7") (pinfunction "C1_(2)_7") (pintype "passive"))
    )
    (net (code "61") (name "Net-(U8-R1)") (class "Default")
      (node (ref "R12") (pin "2") (pinfunction "2_2") (pintype "passive"))
      (node (ref "U8") (pin "11") (pinfunction "R1_11") (pintype "passive"))
    )
    (net (code "62") (name "Net-(U8-R2)") (class "Default")
      (node (ref "R11") (pin "1") (pinfunction "1_1") (pintype "passive"))
      (node (ref "U8") (pin "12") (pinfunction "R2_12") (pintype "passive"))
    )
    (net (code "63") (name "Net-(U8-VCO_In)") (class "Default")
      (node (ref "R9") (pin "2") (pinfunction "2_2") (pintype "passive"))
      (node (ref "U8") (pin "9") (pinfunction "VCO_In_9") (pintype "passive"))
      (node (ref "U9") (pin "1") (pinfunction "Out_A_1") (pintype "power_in"))
    )
    (net (code "64") (name "Net-(U9--In_A)") (class "Default")
      (node (ref "R10") (pin "2") (pinfunction "2_2") (pintype "passive"))
      (node (ref "R9") (pin "1") (pinfunction "1_1") (pintype "passive"))
      (node (ref "U9") (pin "2") (pinfunction "-In_A_2") (pintype "power_in"))
    )
    (net (code "65") (name "unconnected-(T6-Do_not_connect-Pad5)") (class "Default")
      (node (ref "T6") (pin "5") (pinfunction "Do_not_connect_5") (pintype "passive"))
    )
    (net (code "66") (name "unconnected-(T6-Do_not_connect-Pad8)") (class "Default")
      (node (ref "T6") (pin "8") (pinfunction "Do_not_connect_8") (pintype "passive"))
    )
    (net (code "67") (name "unconnected-(T6-N.C.-Pad3)") (class "Default")
      (node (ref "T6") (pin "3") (pinfunction "N.C._3") (pintype "passive"))
    )
    (net (code "68") (name "unconnected-(T6-N.C.-Pad4)") (class "Default")
      (node (ref "T6") (pin "4") (pinfunction "N.C._4") (pintype "passive"))
    )
    (net (code "69") (name "unconnected-(T7-Do_not_connect-Pad5)") (class "Default")
      (node (ref "T7") (pin "5") (pinfunction "Do_not_connect_5") (pintype "passive"))
    )
    (net (code "70") (name "unconnected-(T7-Do_not_connect-Pad8)") (class "Default")
      (node (ref "T7") (pin "8") (pinfunction "Do_not_connect_8") (pintype "passive"))
    )
    (net (code "71") (name "unconnected-(T7-N.C.-Pad3)") (class "Default")
      (node (ref "T7") (pin "3") (pinfunction "N.C._3") (pintype "passive"))
    )
    (net (code "72") (name "unconnected-(T7-N.C.-Pad4)") (class "Default")
      (node (ref "T7") (pin "4") (pinfunction "N.C._4") (pintype "passive"))
    )
    (net (code "73") (name "unconnected-(U6-Comparator_In-Pad3)") (class "Default")
      (node (ref "U6") (pin "3") (pinfunction "Comparator_In_3") (pintype "passive"))
    )
    (net (code "74") (name "unconnected-(U6-Demodulator_Out-Pad10)") (class "Default")
      (node (ref "U6") (pin "10") (pinfunction "Demodulator_Out_10") (pintype "passive"))
    )
    (net (code "75") (name "unconnected-(U6-Phase_Comp_1_Out-Pad2)") (class "Default")
      (node (ref "U6") (pin "2") (pinfunction "Phase_Comp_1_Out_2") (pintype "passive"))
    )
    (net (code "76") (name "unconnected-(U6-Phase_Comp_2_Out-Pad13)") (class "Default")
      (node (ref "U6") (pin "13") (pinfunction "Phase_Comp_2_Out_13") (pintype "passive"))
    )
    (net (code "77") (name "unconnected-(U6-Phase_Pulses-Pad1)") (class "Default")
      (node (ref "U6") (pin "1") (pinfunction "Phase_Pulses_1") (pintype "passive"))
    )
    (net (code "78") (name "unconnected-(U6-Signal_In-Pad14)") (class "Default")
      (node (ref "U6") (pin "14") (pinfunction "Signal_In_14") (pintype "passive"))
    )
    (net (code "79") (name "unconnected-(U6-Zener-Pad15)") (class "Default")
      (node (ref "U6") (pin "15") (pinfunction "Zener_15") (pintype "passive"))
    )
    (net (code "80") (name "unconnected-(U8-Comparator_In-Pad3)") (class "Default")
      (node (ref "U8") (pin "3") (pinfunction "Comparator_In_3") (pintype "passive"))
    )
    (net (code "81") (name "unconnected-(U8-Demodulator_Out-Pad10)") (class "Default")
      (node (ref "U8") (pin "10") (pinfunction "Demodulator_Out_10") (pintype "passive"))
    )
    (net (code "82") (name "unconnected-(U8-Phase_Comp_1_Out-Pad2)") (class "Default")
      (node (ref "U8") (pin "2") (pinfunction "Phase_Comp_1_Out_2") (pintype "passive"))
    )
    (net (code "83") (name "unconnected-(U8-Phase_Comp_2_Out-Pad13)") (class "Default")
      (node (ref "U8") (pin "13") (pinfunction "Phase_Comp_2_Out_13") (pintype "passive"))
    )
    (net (code "84") (name "unconnected-(U8-Phase_Pulses-Pad1)") (class "Default")
      (node (ref "U8") (pin "1") (pinfunction "Phase_Pulses_1") (pintype "passive"))
    )
    (net (code "85") (name "unconnected-(U8-Signal_In-Pad14)") (class "Default")
      (node (ref "U8") (pin "14") (pinfunction "Signal_In_14") (pintype "passive"))
    )
    (net (code "86") (name "unconnected-(U8-Zener-Pad15)") (class "Default")
      (node (ref "U8") (pin "15") (pinfunction "Zener_15") (pintype "passive"))
    )
    (net (code "87") (name "unconnected-(U9-+In_A-Pad5)") (class "Default")
      (node (ref "U9") (pin "5") (pinfunction "+In_A_5") (pintype "power_in"))
    )
    (net (code "88") (name "unconnected-(U9--In_B-Pad6)") (class "Default")
      (node (ref "U9") (pin "6") (pinfunction "-In_B_6") (pintype "power_in"))
    )
    (net (code "89") (name "unconnected-(U9-Out_B-Pad7)") (class "Default")
      (node (ref "U9") (pin "7") (pinfunction "Out_B_7") (pintype "power_in"))
    )
  )
)
